# Alim.net
KiCad netlist of a schematic drawn in Altium Designer
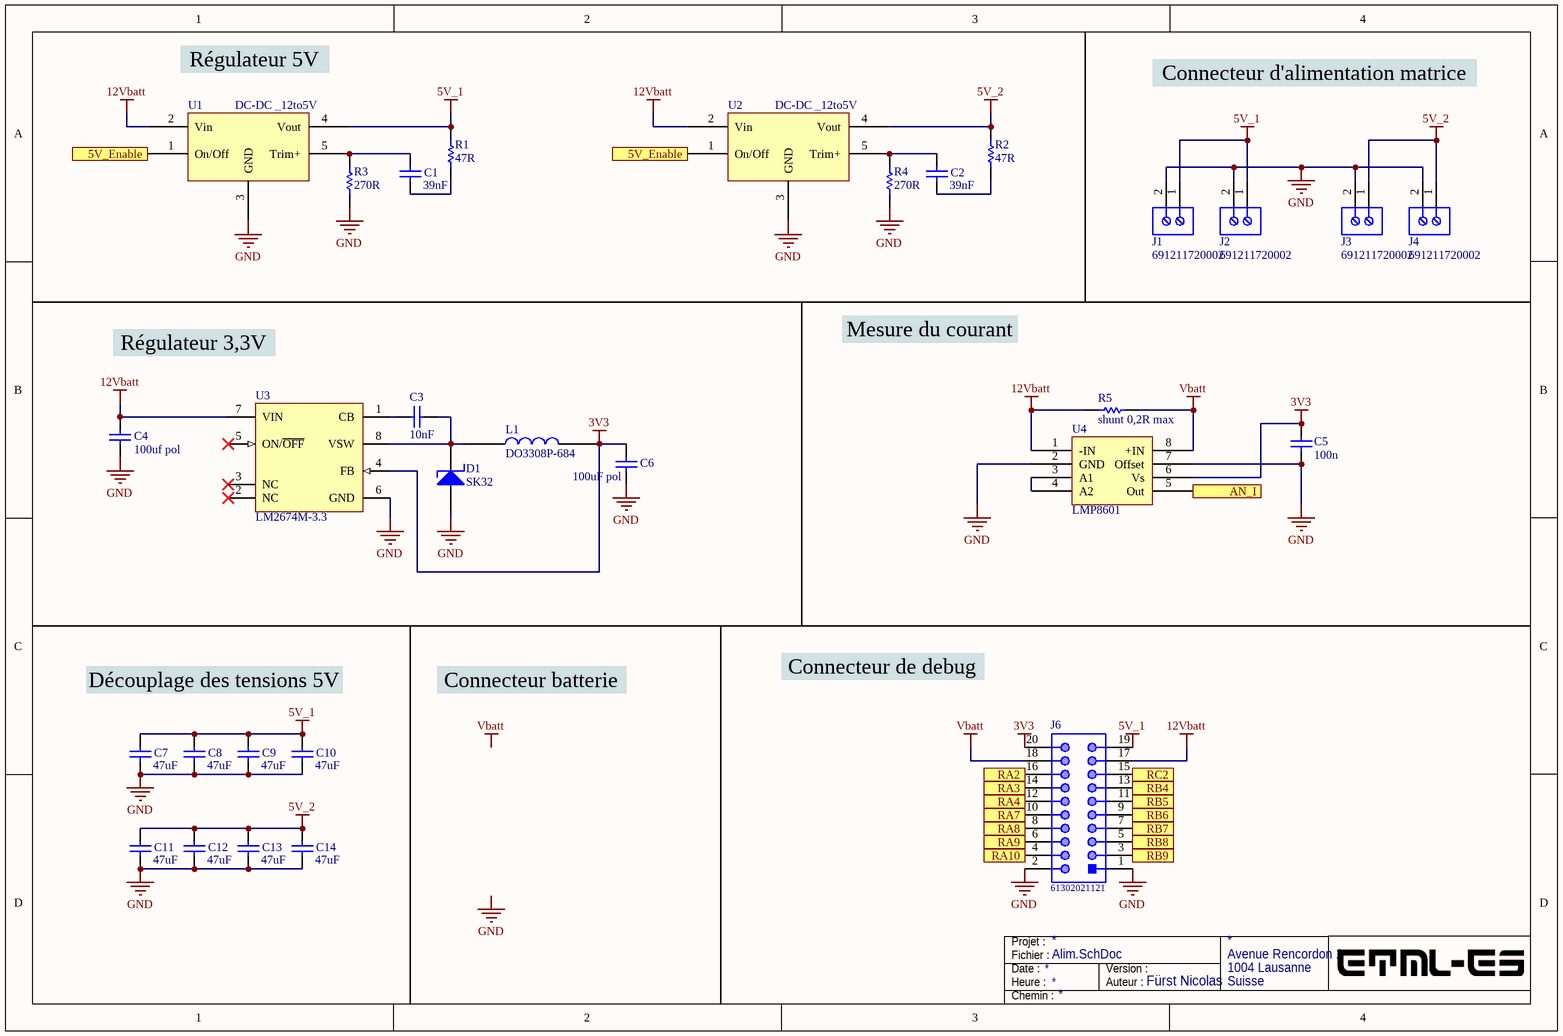
[diagram p0: Alim.SchDoc]

(export (version "E")
  (design (tool "Eeschema 10.0.6"))
  (components
    (comp (ref "C1")
      (value "39nF")
      (footprint "CAPC0805(2012)155_L")
      (fields (field (name "TOLERANCE") "Â±10%"))
      (libsource (lib "Schlib1") (part "Capa"))
    )
    (comp (ref "C2")
      (value "39nF")
      (footprint "CAPC0805(2012)155_L")
      (fields (field (name "TOLERANCE") "Â±10%"))
      (libsource (lib "Schlib1") (part "Capa"))
    )
    (comp (ref "C3")
      (value "10nF")
      (footprint "CAPC0805(2012)155_L")
      (fields (field (name "TOLERANCE") "Â±10%"))
      (libsource (lib "Schlib1") (part "Capa"))
    )
    (comp (ref "C4")
      (value "100uf pol")
      (footprint "CAPC0805(2012)155_L")
      (fields (field (name "TOLERANCE") "Â±10%"))
      (libsource (lib "Schlib1") (part "Capa"))
    )
    (comp (ref "C5")
      (value "100n")
      (footprint "CAPC0805(2012)155_L")
      (fields (field (name "TOLERANCE") "Â±10%"))
      (libsource (lib "Schlib1") (part "Capa"))
    )
    (comp (ref "C6")
      (value "100uF pol")
      (footprint "CAPC0805(2012)155_L")
      (fields (field (name "TOLERANCE") "Â±10%"))
      (libsource (lib "Schlib1") (part "Capa"))
    )
    (comp (ref "C7")
      (value "47uF")
      (footprint "CAPC0805(2012)155_L")
      (fields (field (name "TOLERANCE") "Â±10%"))
      (libsource (lib "Schlib1") (part "Capa"))
    )
    (comp (ref "C8")
      (value "47uF")
      (footprint "CAPC0805(2012)155_L")
      (fields (field (name "TOLERANCE") "Â±10%"))
      (libsource (lib "Schlib1") (part "Capa"))
    )
    (comp (ref "C9")
      (value "47uF")
      (footprint "CAPC0805(2012)155_L")
      (fields (field (name "TOLERANCE") "Â±10%"))
      (libsource (lib "Schlib1") (part "Capa"))
    )
    (comp (ref "C10")
      (value "47uF")
      (footprint "CAPC0805(2012)155_L")
      (fields (field (name "TOLERANCE") "Â±10%"))
      (libsource (lib "Schlib1") (part "Capa"))
    )
    (comp (ref "C11")
      (value "47uF")
      (footprint "CAPC0805(2012)155_L")
      (fields (field (name "TOLERANCE") "Â±10%"))
      (libsource (lib "Schlib1") (part "Capa"))
    )
    (comp (ref "C12")
      (value "47uF")
      (footprint "CAPC0805(2012)155_L")
      (fields (field (name "TOLERANCE") "Â±10%"))
      (libsource (lib "Schlib1") (part "Capa"))
    )
    (comp (ref "C13")
      (value "47uF")
      (footprint "CAPC0805(2012)155_L")
      (fields (field (name "TOLERANCE") "Â±10%"))
      (libsource (lib "Schlib1") (part "Capa"))
    )
    (comp (ref "C14")
      (value "47uF")
      (footprint "CAPC0805(2012)155_L")
      (fields (field (name "TOLERANCE") "Â±10%"))
      (libsource (lib "Schlib1") (part "Capa"))
    )
    (comp (ref "D1")
      (value "SK32")
      (footprint "DO-214AC")
      (description "Shotky diod")
      (fields (field (name "PARTNUMBER") "151031SS04000") (field (name "MANUFACTURER") "Wuerth Elektronik"))
      (libsource (lib "Schlib1") (part "SK32"))
    )
    (comp (ref "J1")
      (value "691211720002")
      (footprint "691211720002")
      (description "Serie 211 - 5.00 mm 45deg Entry Modular with Rising Cage Clamp - 15.50 mm Height WR-TBL, 2 pin")
      (fields (field (name "MANUFACTURER") "Wurth Elektronik") (field (name "PUBLISHER") "WurthElektronik"))
      (libsource (lib "Altium Content Vault") (part "WE-CN-1P-F-TB2"))
    )
    (comp (ref "J2")
      (value "691211720002")
      (footprint "691211720002")
      (description "Serie 211 - 5.00 mm 45deg Entry Modular with Rising Cage Clamp - 15.50 mm Height WR-TBL, 2 pin")
      (fields (field (name "MANUFACTURER") "Wurth Elektronik") (field (name "PUBLISHER") "WurthElektronik"))
      (libsource (lib "Altium Content Vault") (part "WE-CN-1P-F-TB2"))
    )
    (comp (ref "J3")
      (value "691211720002")
      (footprint "691211720002")
      (description "Serie 211 - 5.00 mm 45deg Entry Modular with Rising Cage Clamp - 15.50 mm Height WR-TBL, 2 pin")
      (fields (field (name "MANUFACTURER") "Wurth Elektronik") (field (name "PUBLISHER") "WurthElektronik"))
      (libsource (lib "Altium Content Vault") (part "WE-CN-1P-F-TB2"))
    )
    (comp (ref "J4")
      (value "691211720002")
      (footprint "691211720002")
      (description "Serie 211 - 5.00 mm 45deg Entry Modular with Rising Cage Clamp - 15.50 mm Height WR-TBL, 2 pin")
      (fields (field (name "MANUFACTURER") "Wurth Elektronik") (field (name "PUBLISHER") "WurthElektronik"))
      (libsource (lib "Altium Content Vault") (part "WE-CN-1P-F-TB2"))
    )
    (comp (ref "J6")
      (value "61302021121")
      (footprint "61302021121")
      (description "THT Vertical Pin Header WR-PHD, Pitch 2.54 mm, Dual Row, 20 pins")
      (fields (field (name "MANUFACTURER") "Wurth Elektronik") (field (name "PUBLISHER") "WurthElektronik"))
      (libsource (lib "Altium Content Vault") (part "WE-CN-2P-M-R20"))
    )
    (comp (ref "L1")
      (value "DO3308P-684")
      (footprint "DO3308P")
      (libsource (lib "Schlib1") (part "DO3308P-684"))
    )
    (comp (ref "R1")
      (value "47R")
      (footprint "RESC0805(2012)_N")
      (fields (field (name "POWER") "0.125 W") (field (name "TOLERANCE") "1 %"))
      (libsource (lib "Schlib1") (part "Resistor"))
    )
    (comp (ref "R2")
      (value "47R")
      (footprint "RESC0805(2012)_N")
      (fields (field (name "POWER") "0.125 W") (field (name "TOLERANCE") "1 %"))
      (libsource (lib "Schlib1") (part "Resistor"))
    )
    (comp (ref "R3")
      (value "270R")
      (footprint "RESC0805(2012)_N")
      (fields (field (name "POWER") "0.125 W") (field (name "TOLERANCE") "1 %"))
      (libsource (lib "Schlib1") (part "Resistor"))
    )
    (comp (ref "R4")
      (value "270R")
      (footprint "RESC0805(2012)_N")
      (fields (field (name "POWER") "0.125 W") (field (name "TOLERANCE") "1 %"))
      (libsource (lib "Schlib1") (part "Resistor"))
    )
    (comp (ref "R5")
      (value "shunt 0,2R max")
      (footprint "RESC0805(2012)_N")
      (fields (field (name "POWER") "0.125 W") (field (name "TOLERANCE") "1 %"))
      (libsource (lib "Schlib1") (part "Resistor"))
    )
    (comp (ref "U1")
      (value "DC-DC _12to5V")
      (footprint "61300511121")
      (libsource (lib "Schlib1") (part "DC-DC _12to5V"))
    )
    (comp (ref "U2")
      (value "DC-DC _12to5V")
      (footprint "61300511121")
      (libsource (lib "Schlib1") (part "DC-DC _12to5V"))
    )
    (comp (ref "U3")
      (value "LM2674M-3.3")
      (footprint "M08A_N")
      (fields (field (name "MANUFACTURER") "National Semiconductor"))
      (libsource (lib "Altium Content Vault") (part "PM-REG-LM2674"))
    )
    (comp (ref "U4") (value "LMP8601") (libsource (lib "Schlib1") (part "LMP8601")))
  )
  (nets
    (net (code "1") (name "/5V_Enable") (class "Default")
      (node (ref "U1") (pin "1") (pinfunction "On/Off_1") (pintype "passive"))
      (node (ref "U2") (pin "1") (pinfunction "On/Off_1") (pintype "passive"))
    )
    (net (code "2") (name "/AN_I") (class "Default")
      (node (ref "U4") (pin "5") (pinfunction "Out_5") (pintype "passive"))
    )
    (net (code "3") (name "/RA2") (class "Default")
      (node (ref "J6") (pin "16") (pinfunction "16_16") (pintype "passive"))
    )
    (net (code "4") (name "/RA3") (class "Default")
      (node (ref "J6") (pin "14") (pinfunction "14_14") (pintype "passive"))
    )
    (net (code "5") (name "/RA4") (class "Default")
      (node (ref "J6") (pin "12") (pinfunction "12_12") (pintype "passive"))
    )
    (net (code "6") (name "/RA7") (class "Default")
      (node (ref "J6") (pin "10") (pinfunction "10_10") (pintype "passive"))
    )
    (net (code "7") (name "/RA8") (class "Default")
      (node (ref "J6") (pin "8") (pinfunction "8_8") (pintype "passive"))
    )
    (net (code "8") (name "/RA9") (class "Default")
      (node (ref "J6") (pin "6") (pinfunction "6_6") (pintype "passive"))
    )
    (net (code "9") (name "/RA10") (class "Default")
      (node (ref "J6") (pin "4") (pinfunction "4_4") (pintype "passive"))
    )
    (net (code "10") (name "/RB4") (class "Default")
      (node (ref "J6") (pin "13") (pinfunction "13_13") (pintype "passive"))
    )
    (net (code "11") (name "/RB5") (class "Default")
      (node (ref "J6") (pin "11") (pinfunction "11_11") (pintype "passive"))
    )
    (net (code "12") (name "/RB6") (class "Default")
      (node (ref "J6") (pin "9") (pinfunction "9_9") (pintype "passive"))
    )
    (net (code "13") (name "/RB7") (class "Default")
      (node (ref "J6") (pin "7") (pinfunction "7_7") (pintype "passive"))
    )
    (net (code "14") (name "/RB8") (class "Default")
      (node (ref "J6") (pin "5") (pinfunction "5_5") (pintype "passive"))
    )
    (net (code "15") (name "/RB9") (class "Default")
      (node (ref "J6") (pin "3") (pinfunction "3_3") (pintype "passive"))
    )
    (net (code "16") (name "/RC2") (class "Default")
      (node (ref "J6") (pin "15") (pinfunction "15_15") (pintype "passive"))
    )
    (net (code "17") (name "3V3") (class "Default")
      (node (ref "C5") (pin "1") (pinfunction "1_1") (pintype "passive"))
      (node (ref "C6") (pin "2") (pinfunction "2_2") (pintype "passive"))
      (node (ref "J6") (pin "20") (pinfunction "20_20") (pintype "passive"))
      (node (ref "L1") (pin "2") (pintype "passive"))
      (node (ref "U3") (pin "4") (pinfunction "FB_4") (pintype "input"))
      (node (ref "U4") (pin "6") (pinfunction "Vs_6") (pintype "passive"))
    )
    (net (code "18") (name "5V_1") (class "Default")
      (node (ref "C10") (pin "1") (pinfunction "1_1") (pintype "passive"))
      (node (ref "C7") (pin "1") (pinfunction "1_1") (pintype "passive"))
      (node (ref "C8") (pin "1") (pinfunction "1_1") (pintype "passive"))
      (node (ref "C9") (pin "1") (pinfunction "1_1") (pintype "passive"))
      (node (ref "J1") (pin "1") (pinfunction "1_1") (pintype "passive"))
      (node (ref "J2") (pin "1") (pinfunction "1_1") (pintype "passive"))
      (node (ref "J6") (pin "19") (pinfunction "19_19") (pintype "passive"))
      (node (ref "R1") (pin "2") (pinfunction "2_2") (pintype "passive"))
      (node (ref "U1") (pin "4") (pinfunction "Vout_4") (pintype "passive"))
    )
    (net (code "19") (name "5V_2") (class "Default")
      (node (ref "C11") (pin "1") (pinfunction "1_1") (pintype "passive"))
      (node (ref "C12") (pin "1") (pinfunction "1_1") (pintype "passive"))
      (node (ref "C13") (pin "1") (pinfunction "1_1") (pintype "passive"))
      (node (ref "C14") (pin "1") (pinfunction "1_1") (pintype "passive"))
      (node (ref "J3") (pin "1") (pinfunction "1_1") (pintype "passive"))
      (node (ref "J4") (pin "1") (pinfunction "1_1") (pintype "passive"))
      (node (ref "R2") (pin "2") (pinfunction "2_2") (pintype "passive"))
      (node (ref "U2") (pin "4") (pinfunction "Vout_4") (pintype "passive"))
    )
    (net (code "20") (name "12Vbatt") (class "Default")
      (node (ref "C4") (pin "2") (pinfunction "2_2") (pintype "passive"))
      (node (ref "J6") (pin "17") (pinfunction "17_17") (pintype "passive"))
      (node (ref "R5") (pin "1") (pinfunction "1_1") (pintype "passive"))
      (node (ref "U1") (pin "2") (pinfunction "Vin_2") (pintype "passive"))
      (node (ref "U2") (pin "2") (pinfunction "Vin_2") (pintype "passive"))
      (node (ref "U3") (pin "7") (pinfunction "VIN_7") (pintype "power_in"))
      (node (ref "U4") (pin "1") (pinfunction "-IN_1") (pintype "passive"))
    )
    (net (code "21") (name "GND") (class "Default")
      (node (ref "C10") (pin "2") (pinfunction "2_2") (pintype "passive"))
      (node (ref "C11") (pin "2") (pinfunction "2_2") (pintype "passive"))
      (node (ref "C12") (pin "2") (pinfunction "2_2") (pintype "passive"))
      (node (ref "C13") (pin "2") (pinfunction "2_2") (pintype "passive"))
      (node (ref "C14") (pin "2") (pinfunction "2_2") (pintype "passive"))
      (node (ref "C4") (pin "1") (pinfunction "1_1") (pintype "passive"))
      (node (ref "C5") (pin "2") (pinfunction "2_2") (pintype "passive"))
      (node (ref "C6") (pin "1") (pinfunction "1_1") (pintype "passive"))
      (node (ref "C7") (pin "2") (pinfunction "2_2") (pintype "passive"))
      (node (ref "C8") (pin "2") (pinfunction "2_2") (pintype "passive"))
      (node (ref "C9") (pin "2") (pinfunction "2_2") (pintype "passive"))
      (node (ref "D1") (pin "2") (pinfunction "A_2") (pintype "passive"))
      (node (ref "J1") (pin "2") (pinfunction "2_2") (pintype "passive"))
      (node (ref "J2") (pin "2") (pinfunction "2_2") (pintype "passive"))
      (node (ref "J3") (pin "2") (pinfunction "2_2") (pintype "passive"))
      (node (ref "J4") (pin "2") (pinfunction "2_2") (pintype "passive"))
      (node (ref "J6") (pin "1") (pinfunction "1_1") (pintype "passive"))
      (node (ref "J6") (pin "2") (pinfunction "2_2") (pintype "passive"))
      (node (ref "R3") (pin "1") (pinfunction "1_1") (pintype "passive"))
      (node (ref "R4") (pin "1") (pinfunction "1_1") (pintype "passive"))
      (node (ref "U1") (pin "3") (pinfunction "GND_3") (pintype "passive"))
      (node (ref "U2") (pin "3") (pinfunction "GND_3") (pintype "passive"))
      (node (ref "U3") (pin "6") (pinfunction "GND_6") (pintype "power_in"))
      (node (ref "U4") (pin "2") (pinfunction "GND_2") (pintype "passive"))
      (node (ref "U4") (pin "7") (pinfunction "Offset_7") (pintype "passive"))
    )
    (net (code "22") (name "Net-(C1-Pad2)") (class "Default")
      (node (ref "C1") (pin "2") (pinfunction "2_2") (pintype "passive"))
      (node (ref "R1") (pin "1") (pinfunction "1_1") (pintype "passive"))
    )
    (net (code "23") (name "Net-(C2-Pad1)") (class "Default")
      (node (ref "C2") (pin "1") (pinfunction "1_1") (pintype "passive"))
      (node (ref "R2") (pin "1") (pinfunction "1_1") (pintype "passive"))
    )
    (net (code "24") (name "Net-(D1-K)") (class "Default")
      (node (ref "C3") (pin "2") (pinfunction "2_2") (pintype "passive"))
      (node (ref "D1") (pin "1") (pinfunction "K_1") (pintype "passive"))
      (node (ref "L1") (pin "1") (pintype "passive"))
      (node (ref "U3") (pin "8") (pinfunction "VSW_8") (pintype "power_in"))
    )
    (net (code "25") (name "Net-(U1-Trim+)") (class "Default")
      (node (ref "C1") (pin "1") (pinfunction "1_1") (pintype "passive"))
      (node (ref "R3") (pin "2") (pinfunction "2_2") (pintype "passive"))
      (node (ref "U1") (pin "5") (pinfunction "Trim+_5") (pintype "passive"))
    )
    (net (code "26") (name "Net-(U2-Trim+)") (class "Default")
      (node (ref "C2") (pin "2") (pinfunction "2_2") (pintype "passive"))
      (node (ref "R4") (pin "2") (pinfunction "2_2") (pintype "passive"))
      (node (ref "U2") (pin "5") (pinfunction "Trim+_5") (pintype "passive"))
    )
    (net (code "27") (name "Net-(U3-CB)") (class "Default")
      (node (ref "C3") (pin "1") (pinfunction "1_1") (pintype "passive"))
      (node (ref "U3") (pin "1") (pinfunction "CB_1") (pintype "passive"))
    )
    (net (code "28") (name "Net-(U4-A1)") (class "Default")
      (node (ref "U4") (pin "3") (pinfunction "A1_3") (pintype "passive"))
      (node (ref "U4") (pin "4") (pinfunction "A2_4") (pintype "passive"))
    )
    (net (code "29") (name "Vbatt") (class "Default")
      (node (ref "J6") (pin "18") (pinfunction "18_18") (pintype "passive"))
      (node (ref "R5") (pin "2") (pinfunction "2_2") (pintype "passive"))
      (node (ref "U4") (pin "8") (pinfunction "+IN_8") (pintype "passive"))
    )
    (net (code "30") (name "unconnected-(U3-NC-Pad2)") (class "Default")
      (node (ref "U3") (pin "2") (pinfunction "NC_2") (pintype "passive+no_connect"))
    )
    (net (code "31") (name "unconnected-(U3-NC-Pad3)") (class "Default")
      (node (ref "U3") (pin "3") (pinfunction "NC_3") (pintype "passive+no_connect"))
    )
    (net (code "32") (name "unconnected-(U3-ON{slash}~{OFF}-Pad5)") (class "Default")
      (node (ref "U3") (pin "5") (pinfunction "ON/~{OFF}_5") (pintype "input+no_connect"))
    )
  )
)
